# IA-prop.net
KiCad netlist of a schematic drawn in EAGLE
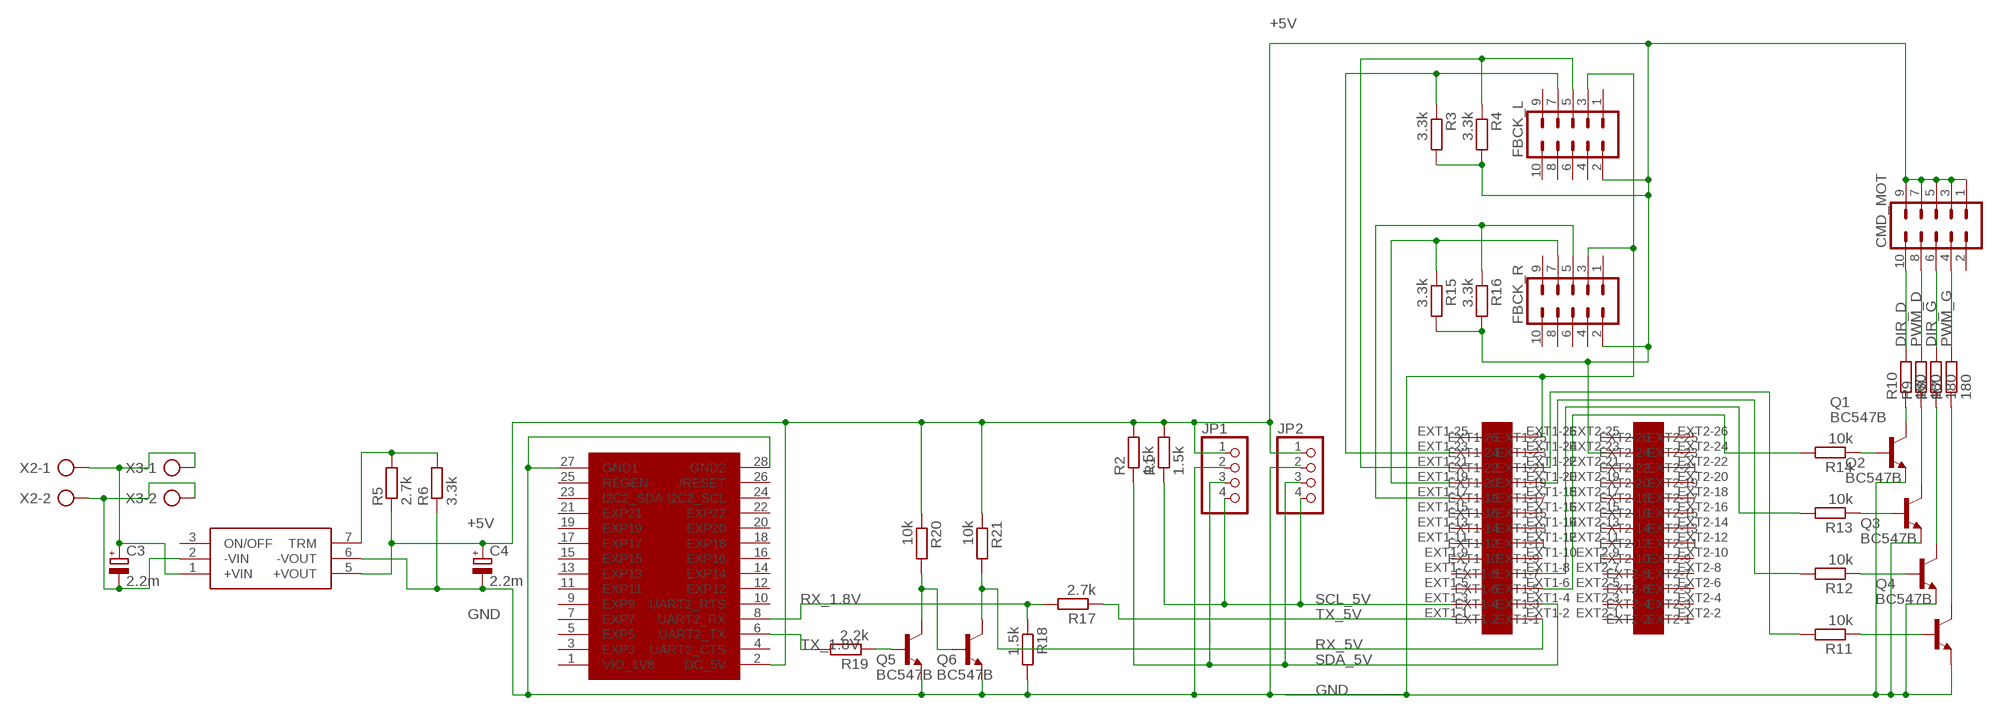
[diagram p0: schematic, sheet 1]

(export (version "E")
  (design (tool "Eeschema 10.0.6"))
  (components
    (comp (ref "BB1")
      (value "BEAGLEBOARD")
      (footprint "eagle-import:BEAGLEBOARD")
      (libsource (lib "eagle-import") (part "BEAGLEBOARD"))
    )
    (comp (ref "C3")
      (value "2.2m")
      (footprint "eagle-import:E5-13")
      (libsource (lib "eagle-import") (part "CPOL-EUE5-13"))
    )
    (comp (ref "C4")
      (value "2.2m")
      (footprint "eagle-import:E5-13")
      (libsource (lib "eagle-import") (part "CPOL-EUE5-13"))
    )
    (comp (ref "CMD_MOT")
      (value "MA05-2")
      (footprint "eagle-import:MA05-2")
      (fields (field (name "OC_FARNELL") "unknown") (field (name "OC_NEWARK") "unknown"))
      (libsource (lib "eagle-import") (part "MA05-2"))
    )
    (comp (ref "FBCK_L")
      (value "MA05-2")
      (footprint "eagle-import:MA05-2")
      (fields (field (name "OC_FARNELL") "unknown") (field (name "OC_NEWARK") "unknown"))
      (libsource (lib "eagle-import") (part "MA05-2"))
    )
    (comp (ref "FBCK_R")
      (value "MA05-2")
      (footprint "eagle-import:MA05-2")
      (fields (field (name "OC_FARNELL") "unknown") (field (name "OC_NEWARK") "unknown"))
      (libsource (lib "eagle-import") (part "MA05-2"))
    )
    (comp (ref "JP1")
      (value "PINHD-1X4")
      (footprint "eagle-import:1X04")
      (libsource (lib "eagle-import") (part "PINHD-1X4"))
    )
    (comp (ref "JP2")
      (value "PINHD-1X4")
      (footprint "eagle-import:1X04")
      (libsource (lib "eagle-import") (part "PINHD-1X4"))
    )
    (comp (ref "Q1")
      (value "BC547B")
      (footprint "eagle-import:TO92")
      (libsource (lib "eagle-import") (part "BC547B"))
    )
    (comp (ref "Q2")
      (value "BC547B")
      (footprint "eagle-import:TO92")
      (libsource (lib "eagle-import") (part "BC547B"))
    )
    (comp (ref "Q3")
      (value "BC547B")
      (footprint "eagle-import:TO92")
      (libsource (lib "eagle-import") (part "BC547B"))
    )
    (comp (ref "Q4")
      (value "BC547B")
      (footprint "eagle-import:TO92")
      (libsource (lib "eagle-import") (part "BC547B"))
    )
    (comp (ref "Q5")
      (value "BC547B")
      (footprint "eagle-import:TO92")
      (libsource (lib "eagle-import") (part "BC547B"))
    )
    (comp (ref "Q6")
      (value "BC547B")
      (footprint "eagle-import:TO92")
      (libsource (lib "eagle-import") (part "BC547B"))
    )
    (comp (ref "R1")
      (value "1.5k")
      (footprint "eagle-import:0207_12")
      (libsource (lib "eagle-import") (part "resistor_R-EU_0207/12"))
    )
    (comp (ref "R2")
      (value "1.5k")
      (footprint "eagle-import:0207_7")
      (libsource (lib "eagle-import") (part "resistor_R-EU_0207/7"))
    )
    (comp (ref "R3")
      (value "3.3k")
      (footprint "eagle-import:0207_7")
      (libsource (lib "eagle-import") (part "R-EU_0207/7"))
    )
    (comp (ref "R4")
      (value "3.3k")
      (footprint "eagle-import:0207_7")
      (libsource (lib "eagle-import") (part "R-EU_0207/7"))
    )
    (comp (ref "R5")
      (value "2.7k")
      (footprint "eagle-import:0207_7")
      (libsource (lib "eagle-import") (part "resistor_R-EU_0207/7"))
    )
    (comp (ref "R6")
      (value "3.3k")
      (footprint "eagle-import:0207_7")
      (libsource (lib "eagle-import") (part "resistor_R-EU_0207/7"))
    )
    (comp (ref "R7")
      (value "180")
      (footprint "eagle-import:0207_7")
      (libsource (lib "eagle-import") (part "R-EU_0207/7"))
    )
    (comp (ref "R8")
      (value "180")
      (footprint "eagle-import:0207_7")
      (libsource (lib "eagle-import") (part "R-EU_0207/7"))
    )
    (comp (ref "R9")
      (value "180")
      (footprint "eagle-import:0207_7")
      (libsource (lib "eagle-import") (part "R-EU_0207/7"))
    )
    (comp (ref "R10")
      (value "180")
      (footprint "eagle-import:0207_7")
      (libsource (lib "eagle-import") (part "R-EU_0207/7"))
    )
    (comp (ref "R11")
      (value "10k")
      (footprint "eagle-import:0207_10")
      (libsource (lib "eagle-import") (part "R-EU_0207/10"))
    )
    (comp (ref "R12")
      (value "10k")
      (footprint "eagle-import:0207_10")
      (libsource (lib "eagle-import") (part "R-EU_0207/10"))
    )
    (comp (ref "R13")
      (value "10k")
      (footprint "eagle-import:0207_7")
      (libsource (lib "eagle-import") (part "R-EU_0207/7"))
    )
    (comp (ref "R14")
      (value "10k")
      (footprint "eagle-import:0207_7")
      (libsource (lib "eagle-import") (part "R-EU_0207/7"))
    )
    (comp (ref "R15")
      (value "3.3k")
      (footprint "eagle-import:0207_7")
      (libsource (lib "eagle-import") (part "R-EU_0207/7"))
    )
    (comp (ref "R16")
      (value "3.3k")
      (footprint "eagle-import:0207_7")
      (libsource (lib "eagle-import") (part "R-EU_0207/7"))
    )
    (comp (ref "R17")
      (value "2.7k")
      (footprint "eagle-import:0207_10")
      (libsource (lib "eagle-import") (part "resistor_R-EU_0207/10"))
    )
    (comp (ref "R18")
      (value "1.5k")
      (footprint "eagle-import:0207_7")
      (libsource (lib "eagle-import") (part "resistor_R-EU_0207/7"))
    )
    (comp (ref "R19")
      (value "2.2k")
      (footprint "eagle-import:0207_7")
      (libsource (lib "eagle-import") (part "resistor_R-EU_0207/7"))
    )
    (comp (ref "R20")
      (value "10k")
      (footprint "eagle-import:0207_7")
      (libsource (lib "eagle-import") (part "resistor_R-EU_0207/7"))
    )
    (comp (ref "R21")
      (value "10k")
      (footprint "eagle-import:0207_7")
      (libsource (lib "eagle-import") (part "resistor_R-EU_0207/7"))
    )
    (comp (ref "U$1")
      (value "LPC-H2148LPC-H2148")
      (footprint "eagle-import:LPC-H2148")
      (libsource (lib "eagle-import") (part "LPC-H2148LPC-H2148"))
    )
    (comp (ref "U$2")
      (value "TEN25-1211TEN25-1211")
      (footprint "eagle-import:TEN25")
      (libsource (lib "eagle-import") (part "TEN25-1211TEN25-1211"))
    )
    (comp (ref "X2")
      (value "AK300/2")
      (footprint "eagle-import:AK300_2")
      (libsource (lib "eagle-import") (part "AK300/2"))
    )
    (comp (ref "X3")
      (value "AK300/2")
      (footprint "eagle-import:AK300_2")
      (libsource (lib "eagle-import") (part "AK300/2"))
    )
  )
  (nets
    (net (code "1") (name "/+5V") (class "Default")
      (node (ref "BB1") (pin "2") (pinfunction "DC_5V_2") (pintype "bidirectional"))
      (node (ref "C4") (pin "+") (pinfunction "+_+") (pintype "passive"))
      (node (ref "CMD_MOT") (pin "1") (pinfunction "1_1") (pintype "passive"))
      (node (ref "CMD_MOT") (pin "3") (pinfunction "3_3") (pintype "passive"))
      (node (ref "CMD_MOT") (pin "5") (pinfunction "5_5") (pintype "passive"))
      (node (ref "CMD_MOT") (pin "7") (pinfunction "7_7") (pintype "passive"))
      (node (ref "CMD_MOT") (pin "9") (pinfunction "9_9") (pintype "passive"))
      (node (ref "FBCK_L") (pin "2") (pinfunction "2_2") (pintype "passive"))
      (node (ref "FBCK_R") (pin "2") (pinfunction "2_2") (pintype "passive"))
      (node (ref "JP1") (pin "1") (pinfunction "1_1") (pintype "passive"))
      (node (ref "JP2") (pin "1") (pinfunction "1_1") (pintype "passive"))
      (node (ref "R1") (pin "2") (pinfunction "2_2") (pintype "passive"))
      (node (ref "R15") (pin "2") (pinfunction "2_2") (pintype "passive"))
      (node (ref "R16") (pin "2") (pinfunction "2_2") (pintype "passive"))
      (node (ref "R2") (pin "2") (pinfunction "2_2") (pintype "passive"))
      (node (ref "R20") (pin "1") (pinfunction "1_1") (pintype "passive"))
      (node (ref "R21") (pin "1") (pinfunction "1_1") (pintype "passive"))
      (node (ref "R3") (pin "2") (pinfunction "2_2") (pintype "passive"))
      (node (ref "R4") (pin "2") (pinfunction "2_2") (pintype "passive"))
      (node (ref "R5") (pin "1") (pinfunction "1_1") (pintype "passive"))
      (node (ref "U$1") (pin "EXT2-23") (pinfunction "EXT2-23_EXT2-23") (pintype "bidirectional"))
      (node (ref "U$2") (pin "5") (pinfunction "+VOUT_5") (pintype "bidirectional"))
    )
    (net (code "2") (name "/DIR_D") (class "Default")
      (node (ref "CMD_MOT") (pin "10") (pinfunction "10_10") (pintype "passive"))
      (node (ref "R10") (pin "2") (pinfunction "2_2") (pintype "passive"))
    )
    (net (code "3") (name "/DIR_G") (class "Default")
      (node (ref "CMD_MOT") (pin "6") (pinfunction "6_6") (pintype "passive"))
      (node (ref "R8") (pin "2") (pinfunction "2_2") (pintype "passive"))
    )
    (net (code "4") (name "/GND") (class "Default")
      (node (ref "BB1") (pin "27") (pinfunction "GND1_27") (pintype "bidirectional"))
      (node (ref "BB1") (pin "28") (pinfunction "GND2_28") (pintype "bidirectional"))
      (node (ref "C4") (pin "-") (pinfunction "-_-") (pintype "passive"))
      (node (ref "FBCK_L") (pin "3") (pinfunction "3_3") (pintype "passive"))
      (node (ref "FBCK_R") (pin "3") (pinfunction "3_3") (pintype "passive"))
      (node (ref "JP1") (pin "2") (pinfunction "2_2") (pintype "passive"))
      (node (ref "JP2") (pin "2") (pinfunction "2_2") (pintype "passive"))
      (node (ref "Q1") (pin "1") (pinfunction "E_1") (pintype "passive"))
      (node (ref "Q2") (pin "1") (pinfunction "E_1") (pintype "passive"))
      (node (ref "Q3") (pin "1") (pinfunction "E_1") (pintype "passive"))
      (node (ref "Q4") (pin "1") (pinfunction "E_1") (pintype "passive"))
      (node (ref "Q5") (pin "1") (pinfunction "E_1") (pintype "passive"))
      (node (ref "Q6") (pin "1") (pinfunction "E_1") (pintype "passive"))
      (node (ref "R18") (pin "2") (pinfunction "2_2") (pintype "passive"))
      (node (ref "R6") (pin "1") (pinfunction "1_1") (pintype "passive"))
      (node (ref "U$1") (pin "EXT1-26") (pinfunction "EXT1-26_EXT1-26") (pintype "bidirectional"))
      (node (ref "U$2") (pin "6") (pinfunction "-VOUT_6") (pintype "bidirectional"))
    )
    (net (code "5") (name "/PWM_D") (class "Default")
      (node (ref "CMD_MOT") (pin "8") (pinfunction "8_8") (pintype "passive"))
      (node (ref "R9") (pin "2") (pinfunction "2_2") (pintype "passive"))
    )
    (net (code "6") (name "/PWM_G") (class "Default")
      (node (ref "CMD_MOT") (pin "4") (pinfunction "4_4") (pintype "passive"))
      (node (ref "R7") (pin "2") (pinfunction "2_2") (pintype "passive"))
    )
    (net (code "7") (name "/RX_1.8V") (class "Default")
      (node (ref "BB1") (pin "8") (pinfunction "UART2_RX_8") (pintype "bidirectional"))
      (node (ref "R17") (pin "2") (pinfunction "2_2") (pintype "passive"))
      (node (ref "R18") (pin "1") (pinfunction "1_1") (pintype "passive"))
    )
    (net (code "8") (name "/RX_5V") (class "Default")
      (node (ref "Q6") (pin "3") (pinfunction "C_3") (pintype "passive"))
      (node (ref "R21") (pin "2") (pinfunction "2_2") (pintype "passive"))
      (node (ref "U$1") (pin "EXT1-2") (pinfunction "EXT1-2_EXT1-2") (pintype "bidirectional"))
    )
    (net (code "9") (name "/SCL_5V") (class "Default")
      (node (ref "JP1") (pin "4") (pinfunction "4_4") (pintype "passive"))
      (node (ref "JP2") (pin "4") (pinfunction "4_4") (pintype "passive"))
      (node (ref "R1") (pin "1") (pinfunction "1_1") (pintype "passive"))
      (node (ref "U$1") (pin "EXT1-3") (pinfunction "EXT1-3_EXT1-3") (pintype "bidirectional"))
    )
    (net (code "10") (name "/SDA_5V") (class "Default")
      (node (ref "JP1") (pin "3") (pinfunction "3_3") (pintype "passive"))
      (node (ref "JP2") (pin "3") (pinfunction "3_3") (pintype "passive"))
      (node (ref "R2") (pin "1") (pinfunction "1_1") (pintype "passive"))
      (node (ref "U$1") (pin "EXT1-4") (pinfunction "EXT1-4_EXT1-4") (pintype "bidirectional"))
    )
    (net (code "11") (name "/TX_1.8V") (class "Default")
      (node (ref "BB1") (pin "6") (pinfunction "UART2_TX_6") (pintype "bidirectional"))
      (node (ref "R19") (pin "2") (pinfunction "2_2") (pintype "passive"))
    )
    (net (code "12") (name "/TX_5V") (class "Default")
      (node (ref "R17") (pin "1") (pinfunction "1_1") (pintype "passive"))
      (node (ref "U$1") (pin "EXT1-1") (pinfunction "EXT1-1_EXT1-1") (pintype "bidirectional"))
    )
    (net (code "13") (name "Net-(FBCK_L-Pad5)") (class "Default")
      (node (ref "FBCK_L") (pin "5") (pinfunction "5_5") (pintype "passive"))
      (node (ref "R4") (pin "1") (pinfunction "1_1") (pintype "passive"))
      (node (ref "U$1") (pin "EXT1-21") (pinfunction "EXT1-21_EXT1-21") (pintype "bidirectional"))
    )
    (net (code "14") (name "Net-(FBCK_L-Pad7)") (class "Default")
      (node (ref "FBCK_L") (pin "7") (pinfunction "7_7") (pintype "passive"))
      (node (ref "R3") (pin "1") (pinfunction "1_1") (pintype "passive"))
      (node (ref "U$1") (pin "EXT1-23") (pinfunction "EXT1-23_EXT1-23") (pintype "bidirectional"))
    )
    (net (code "15") (name "Net-(FBCK_R-Pad5)") (class "Default")
      (node (ref "FBCK_R") (pin "5") (pinfunction "5_5") (pintype "passive"))
      (node (ref "R16") (pin "1") (pinfunction "1_1") (pintype "passive"))
      (node (ref "U$1") (pin "EXT1-17") (pinfunction "EXT1-17_EXT1-17") (pintype "bidirectional"))
    )
    (net (code "16") (name "Net-(FBCK_R-Pad7)") (class "Default")
      (node (ref "FBCK_R") (pin "7") (pinfunction "7_7") (pintype "passive"))
      (node (ref "R15") (pin "1") (pinfunction "1_1") (pintype "passive"))
      (node (ref "U$1") (pin "EXT1-19") (pinfunction "EXT1-19_EXT1-19") (pintype "bidirectional"))
    )
    (net (code "17") (name "Net-(Q1-B)") (class "Default")
      (node (ref "Q1") (pin "2") (pinfunction "B_2") (pintype "passive"))
      (node (ref "R14") (pin "1") (pinfunction "1_1") (pintype "passive"))
    )
    (net (code "18") (name "Net-(Q1-C)") (class "Default")
      (node (ref "Q1") (pin "3") (pinfunction "C_3") (pintype "passive"))
      (node (ref "R10") (pin "1") (pinfunction "1_1") (pintype "passive"))
    )
    (net (code "19") (name "Net-(Q2-B)") (class "Default")
      (node (ref "Q2") (pin "2") (pinfunction "B_2") (pintype "passive"))
      (node (ref "R13") (pin "1") (pinfunction "1_1") (pintype "passive"))
    )
    (net (code "20") (name "Net-(Q2-C)") (class "Default")
      (node (ref "Q2") (pin "3") (pinfunction "C_3") (pintype "passive"))
      (node (ref "R9") (pin "1") (pinfunction "1_1") (pintype "passive"))
    )
    (net (code "21") (name "Net-(Q3-B)") (class "Default")
      (node (ref "Q3") (pin "2") (pinfunction "B_2") (pintype "passive"))
      (node (ref "R12") (pin "1") (pinfunction "1_1") (pintype "passive"))
    )
    (net (code "22") (name "Net-(Q3-C)") (class "Default")
      (node (ref "Q3") (pin "3") (pinfunction "C_3") (pintype "passive"))
      (node (ref "R8") (pin "1") (pinfunction "1_1") (pintype "passive"))
    )
    (net (code "23") (name "Net-(Q4-B)") (class "Default")
      (node (ref "Q4") (pin "2") (pinfunction "B_2") (pintype "passive"))
      (node (ref "R11") (pin "1") (pinfunction "1_1") (pintype "passive"))
    )
    (net (code "24") (name "Net-(Q4-C)") (class "Default")
      (node (ref "Q4") (pin "3") (pinfunction "C_3") (pintype "passive"))
      (node (ref "R7") (pin "1") (pinfunction "1_1") (pintype "passive"))
    )
    (net (code "25") (name "Net-(Q5-B)") (class "Default")
      (node (ref "Q5") (pin "2") (pinfunction "B_2") (pintype "passive"))
      (node (ref "R19") (pin "1") (pinfunction "1_1") (pintype "passive"))
    )
    (net (code "26") (name "Net-(Q5-C)") (class "Default")
      (node (ref "Q5") (pin "3") (pinfunction "C_3") (pintype "passive"))
      (node (ref "Q6") (pin "2") (pinfunction "B_2") (pintype "passive"))
      (node (ref "R20") (pin "2") (pinfunction "2_2") (pintype "passive"))
    )
    (net (code "27") (name "Net-(R11-Pad2)") (class "Default")
      (node (ref "R11") (pin "2") (pinfunction "2_2") (pintype "passive"))
      (node (ref "U$1") (pin "EXT1-22") (pinfunction "EXT1-22_EXT1-22") (pintype "bidirectional"))
    )
    (net (code "28") (name "Net-(R12-Pad2)") (class "Default")
      (node (ref "R12") (pin "2") (pinfunction "2_2") (pintype "passive"))
      (node (ref "U$1") (pin "EXT1-20") (pinfunction "EXT1-20_EXT1-20") (pintype "bidirectional"))
    )
    (net (code "29") (name "Net-(R13-Pad2)") (class "Default")
      (node (ref "R13") (pin "2") (pinfunction "2_2") (pintype "passive"))
      (node (ref "U$1") (pin "EXT1-8") (pinfunction "EXT1-8_EXT1-8") (pintype "bidirectional"))
    )
    (net (code "30") (name "Net-(R14-Pad2)") (class "Default")
      (node (ref "R14") (pin "2") (pinfunction "2_2") (pintype "passive"))
      (node (ref "U$1") (pin "EXT1-6") (pinfunction "EXT1-6_EXT1-6") (pintype "bidirectional"))
    )
    (net (code "31") (name "Net-(U$2-+VIN)") (class "Default")
      (node (ref "C3") (pin "+") (pinfunction "+_+") (pintype "passive"))
      (node (ref "U$2") (pin "1") (pinfunction "+VIN_1") (pintype "bidirectional"))
      (node (ref "X2") (pin "1") (pinfunction "KL_1") (pintype "passive"))
      (node (ref "X3") (pin "1") (pinfunction "KL_1") (pintype "passive"))
    )
    (net (code "32") (name "Net-(U$2--VIN)") (class "Default")
      (node (ref "C3") (pin "-") (pinfunction "-_-") (pintype "passive"))
      (node (ref "U$2") (pin "2") (pinfunction "-VIN_2") (pintype "bidirectional"))
      (node (ref "X2") (pin "2") (pinfunction "KL_2") (pintype "passive"))
      (node (ref "X3") (pin "2") (pinfunction "KL_2") (pintype "passive"))
    )
    (net (code "33") (name "Net-(U$2-TRM)") (class "Default")
      (node (ref "R5") (pin "2") (pinfunction "2_2") (pintype "passive"))
      (node (ref "R6") (pin "2") (pinfunction "2_2") (pintype "passive"))
      (node (ref "U$2") (pin "7") (pinfunction "TRM_7") (pintype "bidirectional"))
    )
    (net (code "34") (name "unconnected-(BB1-EXP3-Pad3)") (class "Default")
      (node (ref "BB1") (pin "3") (pinfunction "EXP3_3") (pintype "bidirectional"))
    )
    (net (code "35") (name "unconnected-(BB1-EXP5-Pad5)") (class "Default")
      (node (ref "BB1") (pin "5") (pinfunction "EXP5_5") (pintype "bidirectional"))
    )
    (net (code "36") (name "unconnected-(BB1-EXP7-Pad7)") (class "Default")
      (node (ref "BB1") (pin "7") (pinfunction "EXP7_7") (pintype "bidirectional"))
    )
    (net (code "37") (name "unconnected-(BB1-EXP9-Pad9)") (class "Default")
      (node (ref "BB1") (pin "9") (pinfunction "EXP9_9") (pintype "bidirectional"))
    )
    (net (code "38") (name "unconnected-(BB1-EXP11-Pad11)") (class "Default")
      (node (ref "BB1") (pin "11") (pinfunction "EXP11_11") (pintype "bidirectional"))
    )
    (net (code "39") (name "unconnected-(BB1-EXP12-Pad12)") (class "Default")
      (node (ref "BB1") (pin "12") (pinfunction "EXP12_12") (pintype "bidirectional"))
    )
    (net (code "40") (name "unconnected-(BB1-EXP13-Pad13)") (class "Default")
      (node (ref "BB1") (pin "13") (pinfunction "EXP13_13") (pintype "bidirectional"))
    )
    (net (code "41") (name "unconnected-(BB1-EXP14-Pad14)") (class "Default")
      (node (ref "BB1") (pin "14") (pinfunction "EXP14_14") (pintype "bidirectional"))
    )
    (net (code "42") (name "unconnected-(BB1-EXP15-Pad15)") (class "Default")
      (node (ref "BB1") (pin "15") (pinfunction "EXP15_15") (pintype "bidirectional"))
    )
    (net (code "43") (name "unconnected-(BB1-EXP16-Pad16)") (class "Default")
      (node (ref "BB1") (pin "16") (pinfunction "EXP16_16") (pintype "bidirectional"))
    )
    (net (code "44") (name "unconnected-(BB1-EXP17-Pad17)") (class "Default")
      (node (ref "BB1") (pin "17") (pinfunction "EXP17_17") (pintype "bidirectional"))
    )
    (net (code "45") (name "unconnected-(BB1-EXP18-Pad18)") (class "Default")
      (node (ref "BB1") (pin "18") (pinfunction "EXP18_18") (pintype "bidirectional"))
    )
    (net (code "46") (name "unconnected-(BB1-EXP19-Pad19)") (class "Default")
      (node (ref "BB1") (pin "19") (pinfunction "EXP19_19") (pintype "bidirectional"))
    )
    (net (code "47") (name "unconnected-(BB1-EXP20-Pad20)") (class "Default")
      (node (ref "BB1") (pin "20") (pinfunction "EXP20_20") (pintype "bidirectional"))
    )
    (net (code "48") (name "unconnected-(BB1-EXP21-Pad21)") (class "Default")
      (node (ref "BB1") (pin "21") (pinfunction "EXP21_21") (pintype "bidirectional"))
    )
    (net (code "49") (name "unconnected-(BB1-EXP22-Pad22)") (class "Default")
      (node (ref "BB1") (pin "22") (pinfunction "EXP22_22") (pintype "bidirectional"))
    )
    (net (code "50") (name "unconnected-(BB1-I2C2_SCL-Pad24)") (class "Default")
      (node (ref "BB1") (pin "24") (pinfunction "I2C2_SCL_24") (pintype "bidirectional"))
    )
    (net (code "51") (name "unconnected-(BB1-I2C2_SDA-Pad23)") (class "Default")
      (node (ref "BB1") (pin "23") (pinfunction "I2C2_SDA_23") (pintype "bidirectional"))
    )
    (net (code "52") (name "unconnected-(BB1-REGEN-Pad25)") (class "Default")
      (node (ref "BB1") (pin "25") (pinfunction "REGEN_25") (pintype "bidirectional"))
    )
    (net (code "53") (name "unconnected-(BB1-UART2_CTS-Pad4)") (class "Default")
      (node (ref "BB1") (pin "4") (pinfunction "UART2_CTS_4") (pintype "bidirectional"))
    )
    (net (code "54") (name "unconnected-(BB1-UART2_RTS-Pad10)") (class "Default")
      (node (ref "BB1") (pin "10") (pinfunction "UART2_RTS_10") (pintype "bidirectional"))
    )
    (net (code "55") (name "unconnected-(BB1-VIO_1V8-Pad1)") (class "Default")
      (node (ref "BB1") (pin "1") (pinfunction "VIO_1V8_1") (pintype "bidirectional"))
    )
    (net (code "56") (name "unconnected-(BB1-{slash}RESET-Pad26)") (class "Default")
      (node (ref "BB1") (pin "26") (pinfunction "/RESET_26") (pintype "bidirectional"))
    )
    (net (code "57") (name "unconnected-(CMD_MOT-Pad2)") (class "Default")
      (node (ref "CMD_MOT") (pin "2") (pinfunction "2_2") (pintype "passive"))
    )
    (net (code "58") (name "unconnected-(FBCK_L-Pad1)") (class "Default")
      (node (ref "FBCK_L") (pin "1") (pinfunction "1_1") (pintype "passive"))
    )
    (net (code "59") (name "unconnected-(FBCK_L-Pad4)") (class "Default")
      (node (ref "FBCK_L") (pin "4") (pinfunction "4_4") (pintype "passive"))
    )
    (net (code "60") (name "unconnected-(FBCK_L-Pad6)") (class "Default")
      (node (ref "FBCK_L") (pin "6") (pinfunction "6_6") (pintype "passive"))
    )
    (net (code "61") (name "unconnected-(FBCK_L-Pad8)") (class "Default")
      (node (ref "FBCK_L") (pin "8") (pinfunction "8_8") (pintype "passive"))
    )
    (net (code "62") (name "unconnected-(FBCK_L-Pad9)") (class "Default")
      (node (ref "FBCK_L") (pin "9") (pinfunction "9_9") (pintype "passive"))
    )
    (net (code "63") (name "unconnected-(FBCK_L-Pad10)") (class "Default")
      (node (ref "FBCK_L") (pin "10") (pinfunction "10_10") (pintype "passive"))
    )
    (net (code "64") (name "unconnected-(FBCK_R-Pad1)") (class "Default")
      (node (ref "FBCK_R") (pin "1") (pinfunction "1_1") (pintype "passive"))
    )
    (net (code "65") (name "unconnected-(FBCK_R-Pad4)") (class "Default")
      (node (ref "FBCK_R") (pin "4") (pinfunction "4_4") (pintype "passive"))
    )
    (net (code "66") (name "unconnected-(FBCK_R-Pad6)") (class "Default")
      (node (ref "FBCK_R") (pin "6") (pinfunction "6_6") (pintype "passive"))
    )
    (net (code "67") (name "unconnected-(FBCK_R-Pad8)") (class "Default")
      (node (ref "FBCK_R") (pin "8") (pinfunction "8_8") (pintype "passive"))
    )
    (net (code "68") (name "unconnected-(FBCK_R-Pad9)") (class "Default")
      (node (ref "FBCK_R") (pin "9") (pinfunction "9_9") (pintype "passive"))
    )
    (net (code "69") (name "unconnected-(FBCK_R-Pad10)") (class "Default")
      (node (ref "FBCK_R") (pin "10") (pinfunction "10_10") (pintype "passive"))
    )
    (net (code "70") (name "unconnected-(U$1-PadEXT1-5)") (class "Default")
      (node (ref "U$1") (pin "EXT1-5") (pinfunction "EXT1-5_EXT1-5") (pintype "bidirectional"))
    )
    (net (code "71") (name "unconnected-(U$1-PadEXT1-7)") (class "Default")
      (node (ref "U$1") (pin "EXT1-7") (pinfunction "EXT1-7_EXT1-7") (pintype "bidirectional"))
    )
    (net (code "72") (name "unconnected-(U$1-PadEXT1-9)") (class "Default")
      (node (ref "U$1") (pin "EXT1-9") (pinfunction "EXT1-9_EXT1-9") (pintype "bidirectional"))
    )
    (net (code "73") (name "unconnected-(U$1-PadEXT1-10)") (class "Default")
      (node (ref "U$1") (pin "EXT1-10") (pinfunction "EXT1-10_EXT1-10") (pintype "bidirectional"))
    )
    (net (code "74") (name "unconnected-(U$1-PadEXT1-11)") (class "Default")
      (node (ref "U$1") (pin "EXT1-11") (pinfunction "EXT1-11_EXT1-11") (pintype "bidirectional"))
    )
    (net (code "75") (name "unconnected-(U$1-PadEXT1-12)") (class "Default")
      (node (ref "U$1") (pin "EXT1-12") (pinfunction "EXT1-12_EXT1-12") (pintype "bidirectional"))
    )
    (net (code "76") (name "unconnected-(U$1-PadEXT1-13)") (class "Default")
      (node (ref "U$1") (pin "EXT1-13") (pinfunction "EXT1-13_EXT1-13") (pintype "bidirectional"))
    )
    (net (code "77") (name "unconnected-(U$1-PadEXT1-14)") (class "Default")
      (node (ref "U$1") (pin "EXT1-14") (pinfunction "EXT1-14_EXT1-14") (pintype "bidirectional"))
    )
    (net (code "78") (name "unconnected-(U$1-PadEXT1-15)") (class "Default")
      (node (ref "U$1") (pin "EXT1-15") (pinfunction "EXT1-15_EXT1-15") (pintype "bidirectional"))
    )
    (net (code "79") (name "unconnected-(U$1-PadEXT1-16)") (class "Default")
      (node (ref "U$1") (pin "EXT1-16") (pinfunction "EXT1-16_EXT1-16") (pintype "bidirectional"))
    )
    (net (code "80") (name "unconnected-(U$1-PadEXT1-18)") (class "Default")
      (node (ref "U$1") (pin "EXT1-18") (pinfunction "EXT1-18_EXT1-18") (pintype "bidirectional"))
    )
    (net (code "81") (name "unconnected-(U$1-PadEXT1-24)") (class "Default")
      (node (ref "U$1") (pin "EXT1-24") (pinfunction "EXT1-24_EXT1-24") (pintype "bidirectional"))
    )
    (net (code "82") (name "unconnected-(U$1-PadEXT1-25)") (class "Default")
      (node (ref "U$1") (pin "EXT1-25") (pinfunction "EXT1-25_EXT1-25") (pintype "bidirectional"))
    )
    (net (code "83") (name "unconnected-(U$1-PadEXT2-1)") (class "Default")
      (node (ref "U$1") (pin "EXT2-1") (pinfunction "EXT2-1_EXT2-1") (pintype "bidirectional"))
    )
    (net (code "84") (name "unconnected-(U$1-PadEXT2-2)") (class "Default")
      (node (ref "U$1") (pin "EXT2-2") (pinfunction "EXT2-2_EXT2-2") (pintype "bidirectional"))
    )
    (net (code "85") (name "unconnected-(U$1-PadEXT2-3)") (class "Default")
      (node (ref "U$1") (pin "EXT2-3") (pinfunction "EXT2-3_EXT2-3") (pintype "bidirectional"))
    )
    (net (code "86") (name "unconnected-(U$1-PadEXT2-4)") (class "Default")
      (node (ref "U$1") (pin "EXT2-4") (pinfunction "EXT2-4_EXT2-4") (pintype "bidirectional"))
    )
    (net (code "87") (name "unconnected-(U$1-PadEXT2-5)") (class "Default")
      (node (ref "U$1") (pin "EXT2-5") (pinfunction "EXT2-5_EXT2-5") (pintype "bidirectional"))
    )
    (net (code "88") (name "unconnected-(U$1-PadEXT2-6)") (class "Default")
      (node (ref "U$1") (pin "EXT2-6") (pinfunction "EXT2-6_EXT2-6") (pintype "bidirectional"))
    )
    (net (code "89") (name "unconnected-(U$1-PadEXT2-7)") (class "Default")
      (node (ref "U$1") (pin "EXT2-7") (pinfunction "EXT2-7_EXT2-7") (pintype "bidirectional"))
    )
    (net (code "90") (name "unconnected-(U$1-PadEXT2-8)") (class "Default")
      (node (ref "U$1") (pin "EXT2-8") (pinfunction "EXT2-8_EXT2-8") (pintype "bidirectional"))
    )
    (net (code "91") (name "unconnected-(U$1-PadEXT2-9)") (class "Default")
      (node (ref "U$1") (pin "EXT2-9") (pinfunction "EXT2-9_EXT2-9") (pintype "bidirectional"))
    )
    (net (code "92") (name "unconnected-(U$1-PadEXT2-10)") (class "Default")
      (node (ref "U$1") (pin "EXT2-10") (pinfunction "EXT2-10_EXT2-10") (pintype "bidirectional"))
    )
    (net (code "93") (name "unconnected-(U$1-PadEXT2-11)") (class "Default")
      (node (ref "U$1") (pin "EXT2-11") (pinfunction "EXT2-11_EXT2-11") (pintype "bidirectional"))
    )
    (net (code "94") (name "unconnected-(U$1-PadEXT2-12)") (class "Default")
      (node (ref "U$1") (pin "EXT2-12") (pinfunction "EXT2-12_EXT2-12") (pintype "bidirectional"))
    )
    (net (code "95") (name "unconnected-(U$1-PadEXT2-13)") (class "Default")
      (node (ref "U$1") (pin "EXT2-13") (pinfunction "EXT2-13_EXT2-13") (pintype "bidirectional"))
    )
    (net (code "96") (name "unconnected-(U$1-PadEXT2-14)") (class "Default")
      (node (ref "U$1") (pin "EXT2-14") (pinfunction "EXT2-14_EXT2-14") (pintype "bidirectional"))
    )
    (net (code "97") (name "unconnected-(U$1-PadEXT2-15)") (class "Default")
      (node (ref "U$1") (pin "EXT2-15") (pinfunction "EXT2-15_EXT2-15") (pintype "bidirectional"))
    )
    (net (code "98") (name "unconnected-(U$1-PadEXT2-16)") (class "Default")
      (node (ref "U$1") (pin "EXT2-16") (pinfunction "EXT2-16_EXT2-16") (pintype "bidirectional"))
    )
    (net (code "99") (name "unconnected-(U$1-PadEXT2-17)") (class "Default")
      (node (ref "U$1") (pin "EXT2-17") (pinfunction "EXT2-17_EXT2-17") (pintype "bidirectional"))
    )
    (net (code "100") (name "unconnected-(U$1-PadEXT2-18)") (class "Default")
      (node (ref "U$1") (pin "EXT2-18") (pinfunction "EXT2-18_EXT2-18") (pintype "bidirectional"))
    )
    (net (code "101") (name "unconnected-(U$1-PadEXT2-19)") (class "Default")
      (node (ref "U$1") (pin "EXT2-19") (pinfunction "EXT2-19_EXT2-19") (pintype "bidirectional"))
    )
    (net (code "102") (name "unconnected-(U$1-PadEXT2-20)") (class "Default")
      (node (ref "U$1") (pin "EXT2-20") (pinfunction "EXT2-20_EXT2-20") (pintype "bidirectional"))
    )
    (net (code "103") (name "unconnected-(U$1-PadEXT2-21)") (class "Default")
      (node (ref "U$1") (pin "EXT2-21") (pinfunction "EXT2-21_EXT2-21") (pintype "bidirectional"))
    )
    (net (code "104") (name "unconnected-(U$1-PadEXT2-22)") (class "Default")
      (node (ref "U$1") (pin "EXT2-22") (pinfunction "EXT2-22_EXT2-22") (pintype "bidirectional"))
    )
    (net (code "105") (name "unconnected-(U$1-PadEXT2-24)") (class "Default")
      (node (ref "U$1") (pin "EXT2-24") (pinfunction "EXT2-24_EXT2-24") (pintype "bidirectional"))
    )
    (net (code "106") (name "unconnected-(U$1-PadEXT2-25)") (class "Default")
      (node (ref "U$1") (pin "EXT2-25") (pinfunction "EXT2-25_EXT2-25") (pintype "bidirectional"))
    )
    (net (code "107") (name "unconnected-(U$1-PadEXT2-26)") (class "Default")
      (node (ref "U$1") (pin "EXT2-26") (pinfunction "EXT2-26_EXT2-26") (pintype "bidirectional"))
    )
    (net (code "108") (name "unconnected-(U$2-ON{slash}OFF-Pad3)") (class "Default")
      (node (ref "U$2") (pin "3") (pinfunction "ON/OFF_3") (pintype "bidirectional"))
    )
  )
)
